# 1BUF_1.net
KiCad netlist of a schematic drawn in EAGLE
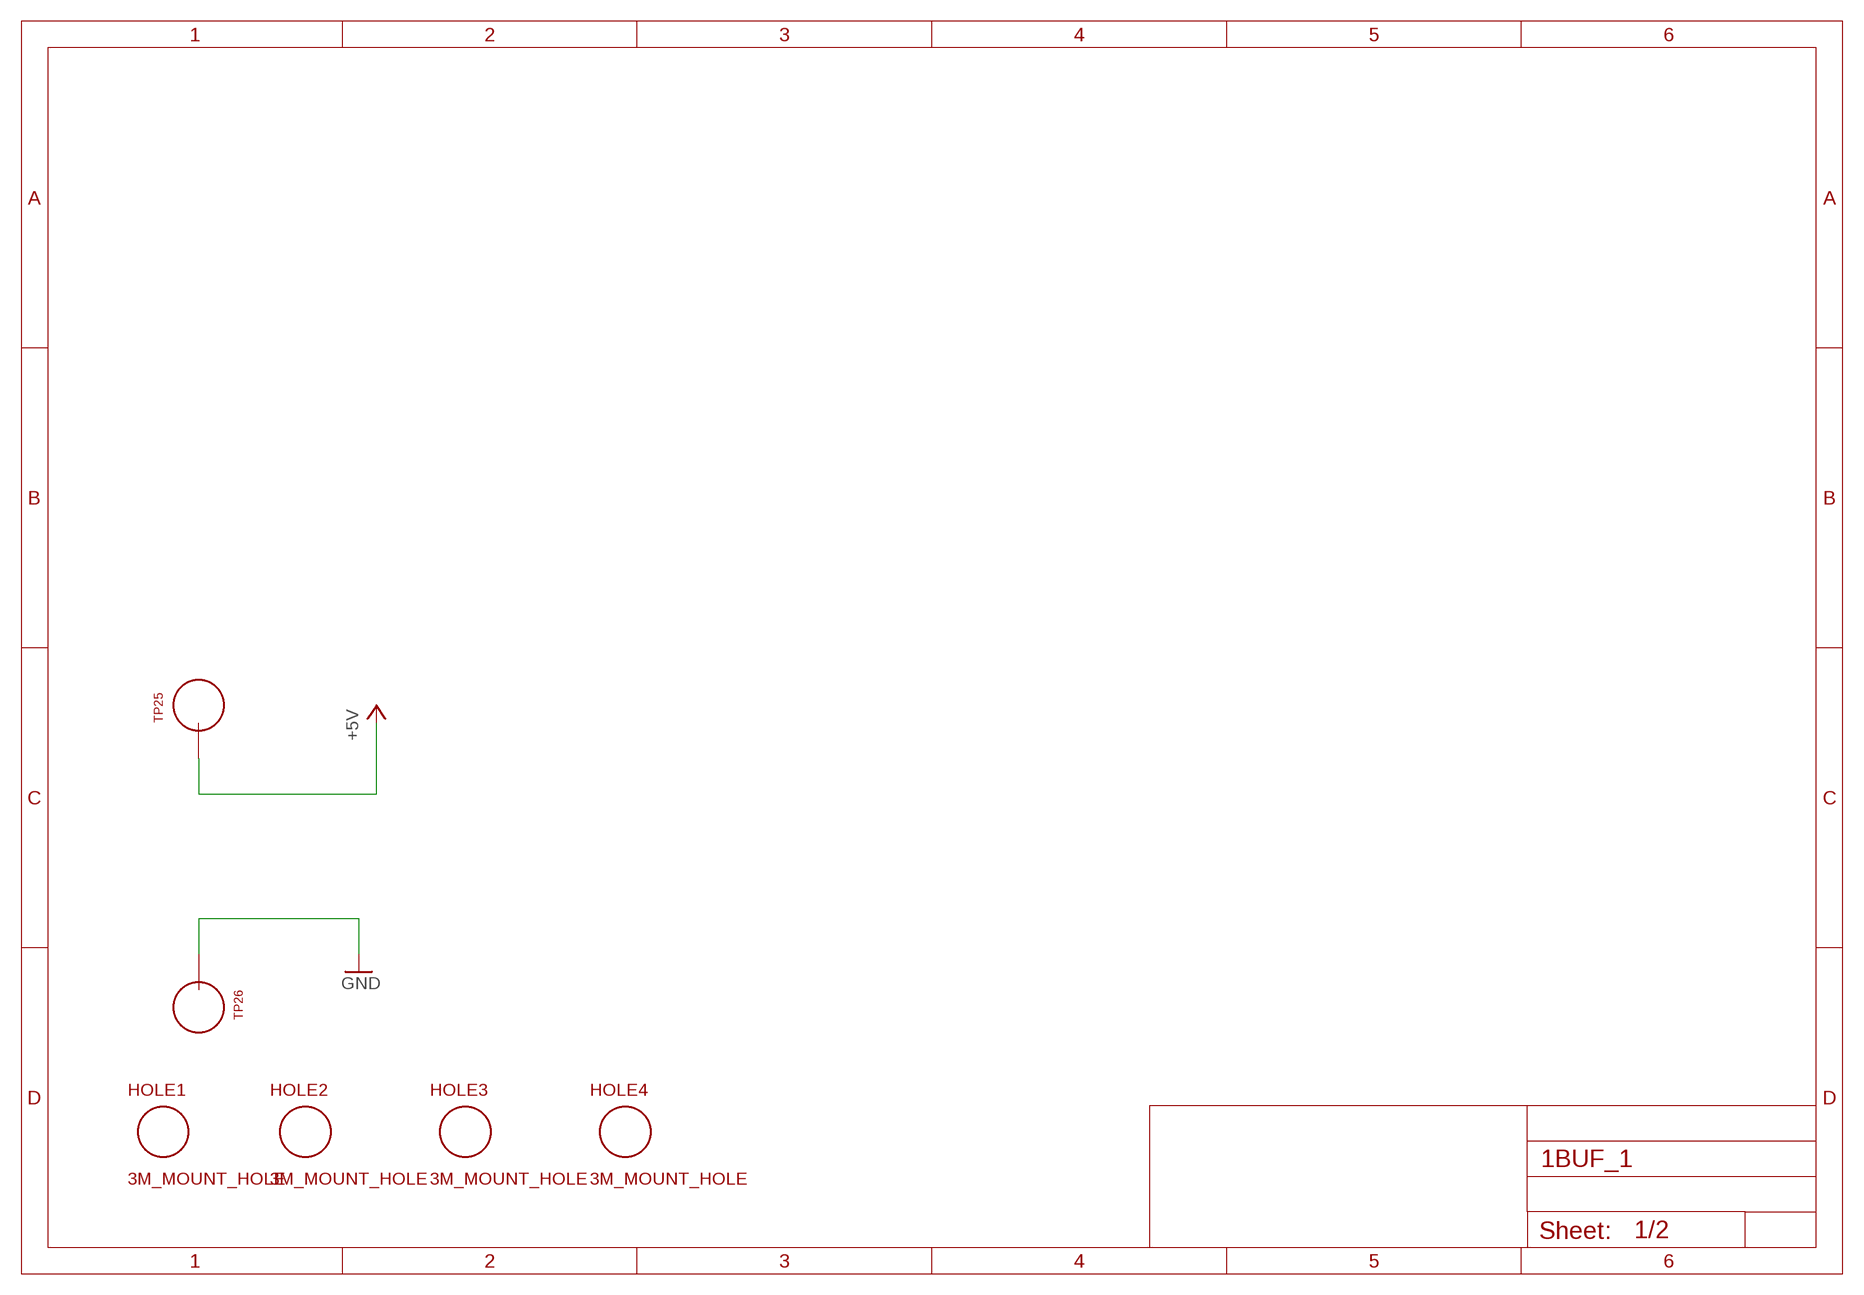
[diagram p0: schematic, sheet 1]
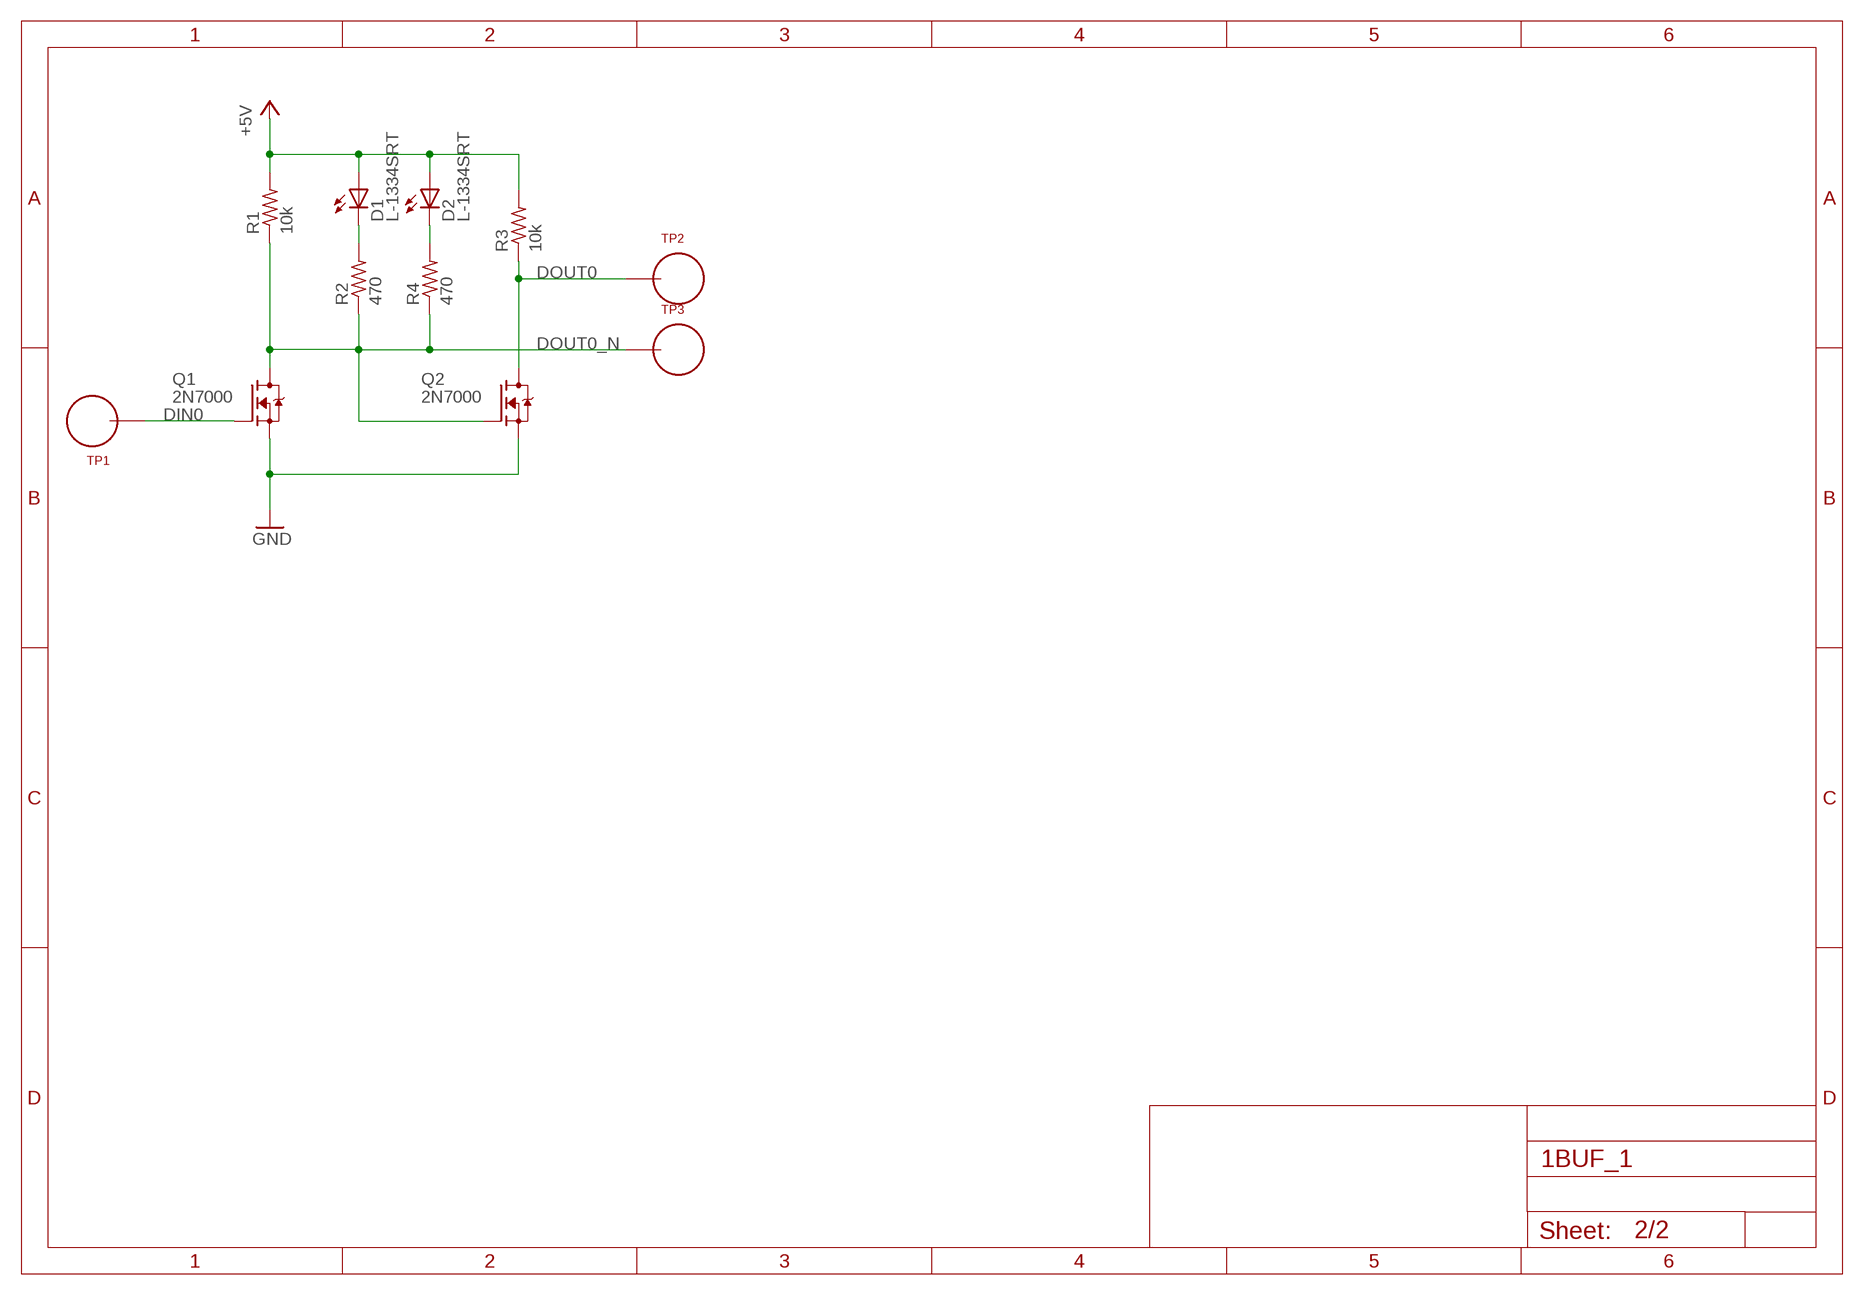
[diagram p1: schematic, sheet 2]

(export (version "E")
  (design (tool "Eeschema 10.0.6"))
  (components
    (comp (ref "HOLE1")
      (value "3M_MOUNT_HOLE")
      (footprint "eagle-import:3M_HOLE")
      (libsource (lib "eagle-import") (part "3M_MOUNT_HOLE"))
    )
    (comp (ref "HOLE2")
      (value "3M_MOUNT_HOLE")
      (footprint "eagle-import:3M_HOLE")
      (libsource (lib "eagle-import") (part "3M_MOUNT_HOLE"))
    )
    (comp (ref "HOLE3")
      (value "3M_MOUNT_HOLE")
      (footprint "eagle-import:3M_HOLE")
      (libsource (lib "eagle-import") (part "3M_MOUNT_HOLE"))
    )
    (comp (ref "HOLE4")
      (value "3M_MOUNT_HOLE")
      (footprint "eagle-import:3M_HOLE")
      (libsource (lib "eagle-import") (part "3M_MOUNT_HOLE"))
    )
    (comp (ref "TP25")
      (value "TEST_LOOP")
      (footprint "eagle-import:TEST_LOOP")
      (libsource (lib "eagle-import") (part "TEST_LOOP"))
    )
    (comp (ref "TP26")
      (value "TEST_LOOP")
      (footprint "eagle-import:TEST_LOOP")
      (libsource (lib "eagle-import") (part "TEST_LOOP"))
    )
    (comp (ref "D1")
      (value "L-1334SRT")
      (footprint "eagle-import:LED3MM")
      (libsource (lib "eagle-import") (part "L-1334SRT"))
    )
    (comp (ref "D2")
      (value "L-1334SRT")
      (footprint "eagle-import:LED3MM")
      (libsource (lib "eagle-import") (part "L-1334SRT"))
    )
    (comp (ref "Q1")
      (value "2N7000")
      (footprint "eagle-import:TO92-DGS")
      (libsource (lib "eagle-import") (part "2N7000"))
    )
    (comp (ref "Q2")
      (value "2N7000")
      (footprint "eagle-import:TO92-DGS")
      (libsource (lib "eagle-import") (part "2N7000"))
    )
    (comp (ref "R1")
      (value "10k")
      (footprint "eagle-import:R_P2INCH")
      (libsource (lib "eagle-import") (part "R_P2INCH"))
    )
    (comp (ref "R2")
      (value "470")
      (footprint "eagle-import:R_P2INCH")
      (libsource (lib "eagle-import") (part "R_P2INCH"))
    )
    (comp (ref "R3")
      (value "10k")
      (footprint "eagle-import:R_P2INCH")
      (libsource (lib "eagle-import") (part "R_P2INCH"))
    )
    (comp (ref "R4")
      (value "470")
      (footprint "eagle-import:R_P2INCH")
      (libsource (lib "eagle-import") (part "R_P2INCH"))
    )
    (comp (ref "TP1")
      (value "TEST_LOOP")
      (footprint "eagle-import:TEST_LOOP")
      (libsource (lib "eagle-import") (part "TEST_LOOP"))
    )
    (comp (ref "TP2")
      (value "TEST_LOOP")
      (footprint "eagle-import:TEST_LOOP")
      (libsource (lib "eagle-import") (part "TEST_LOOP"))
    )
    (comp (ref "TP3")
      (value "TEST_LOOP")
      (footprint "eagle-import:TEST_LOOP")
      (libsource (lib "eagle-import") (part "TEST_LOOP"))
    )
  )
  (nets
    (net (code "1") (name "+5V") (class "Default")
      (node (ref "D1") (pin "A") (pinfunction "A_A") (pintype "passive"))
      (node (ref "D2") (pin "A") (pinfunction "A_A") (pintype "passive"))
      (node (ref "R1") (pin "2") (pinfunction "2_2") (pintype "passive"))
      (node (ref "R3") (pin "2") (pinfunction "2_2") (pintype "passive"))
      (node (ref "TP25") (pin "P$1") (pinfunction "P$1_P$1") (pintype "bidirectional"))
    )
    (net (code "2") (name "DIN0") (class "Default")
      (node (ref "Q1") (pin "G") (pinfunction "G_G") (pintype "passive"))
      (node (ref "TP1") (pin "P$1") (pinfunction "P$1_P$1") (pintype "bidirectional"))
    )
    (net (code "3") (name "DOUT0") (class "Default")
      (node (ref "Q2") (pin "D") (pinfunction "D_D") (pintype "passive"))
      (node (ref "R3") (pin "1") (pinfunction "1_1") (pintype "passive"))
      (node (ref "TP2") (pin "P$1") (pinfunction "P$1_P$1") (pintype "bidirectional"))
    )
    (net (code "4") (name "DOUT0_N") (class "Default")
      (node (ref "Q1") (pin "D") (pinfunction "D_D") (pintype "passive"))
      (node (ref "Q2") (pin "G") (pinfunction "G_G") (pintype "passive"))
      (node (ref "R1") (pin "1") (pinfunction "1_1") (pintype "passive"))
      (node (ref "R2") (pin "1") (pinfunction "1_1") (pintype "passive"))
      (node (ref "R4") (pin "1") (pinfunction "1_1") (pintype "passive"))
      (node (ref "TP3") (pin "P$1") (pinfunction "P$1_P$1") (pintype "bidirectional"))
    )
    (net (code "5") (name "GND") (class "Default")
      (node (ref "Q1") (pin "S") (pinfunction "S_S") (pintype "passive"))
      (node (ref "Q2") (pin "S") (pinfunction "S_S") (pintype "passive"))
      (node (ref "TP26") (pin "P$1") (pinfunction "P$1_P$1") (pintype "bidirectional"))
    )
    (net (code "6") (name "Net-(D1-C)") (class "Default")
      (node (ref "D1") (pin "K") (pinfunction "C_K") (pintype "passive"))
      (node (ref "R2") (pin "2") (pinfunction "2_2") (pintype "passive"))
    )
    (net (code "7") (name "Net-(D2-C)") (class "Default")
      (node (ref "D2") (pin "K") (pinfunction "C_K") (pintype "passive"))
      (node (ref "R4") (pin "2") (pinfunction "2_2") (pintype "passive"))
    )
  )
)
